# MCU023_XDS110_USB_Power.net
KiCad netlist of a schematic drawn in Altium Designer
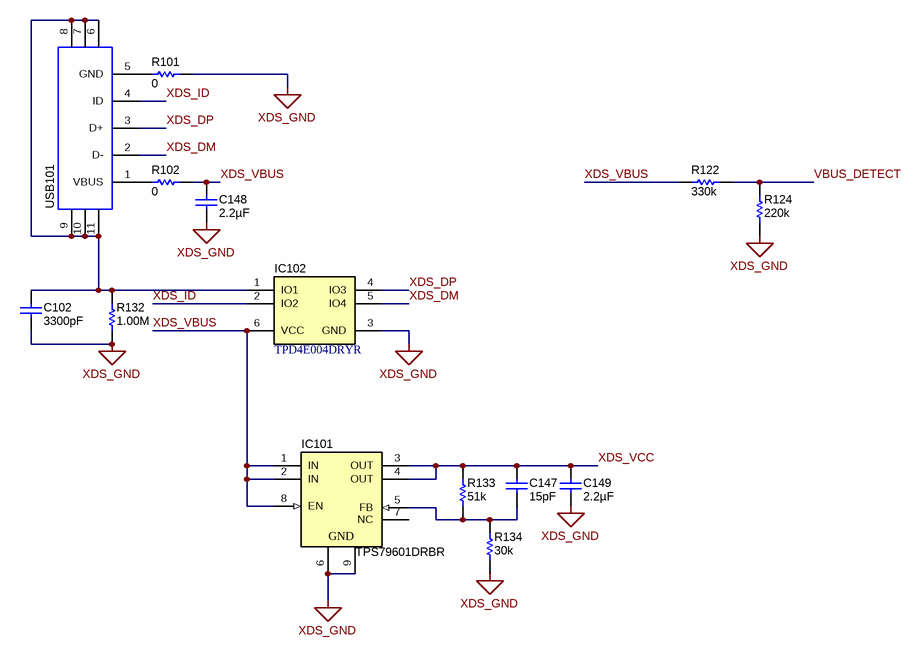
[diagram p0: MCU023_XDS110_USB_Power.SchDoc]

(export (version "E")
  (design (tool "Eeschema 10.0.6"))
  (components
    (comp (ref "C102")
      (value "GRM155R71H332KA01D")
      (footprint "0402")
      (description "CAP, CERM, 3300 pF, 50 V, +/- 10%, X7R, 0402")
      (fields
        (field (name "VALUEDISPLAYED") "3300pF")
        (field (name "MANUFACTURER") "MuRata")
        (field (name "PUBLISHER") "Texas Instruments")
      )
      (libsource (lib "Capacitor_Ceramic") (part "GRM155R71H332KA01D"))
    )
    (comp (ref "C147")
      (value "GRM1555C1H150JA01D")
      (footprint "0402")
      (description "CAP, CERM, 15 pF, 50 V, +/- 5%, C0G/NP0, 0402")
      (fields
        (field (name "VALUEDISPLAYED") "15pF")
        (field (name "MANUFACTURER") "MuRata")
        (field (name "PUBLISHER") "Texas Instruments")
      )
      (libsource (lib "Capacitor_Ceramic") (part "GRM1555C1H150JA01D"))
    )
    (comp (ref "C148")
      (value "GRM155R60J225KE95D")
      (footprint "0402")
      (description "CAP, CERM, 2.2 µF, 6.3 V, +/- 10%, X5R, 0402")
      (fields
        (field (name "VALUEDISPLAYED") "2.2µF")
        (field (name "MANUFACTURER") "MuRata")
        (field (name "PUBLISHER") "Texas Instruments")
      )
      (libsource (lib "Capacitor_Ceramic") (part "GRM155R60J225KE95D"))
    )
    (comp (ref "C149")
      (value "GRM155R60J225KE95D")
      (footprint "0402")
      (description "CAP, CERM, 2.2 µF, 6.3 V, +/- 10%, X5R, 0402")
      (fields
        (field (name "VALUEDISPLAYED") "2.2µF")
        (field (name "MANUFACTURER") "MuRata")
        (field (name "PUBLISHER") "Texas Instruments")
      )
      (libsource (lib "Capacitor_Ceramic") (part "GRM155R60J225KE95D"))
    )
    (comp (ref "IC101")
      (value "TPS79601DRBR")
      (footprint "DRB0008B")
      (fields
        (field (name "MANUFACTURER") "Texas Instruments")
        (field (name "ALTERNATE PARTNUMBER") "Equivalent")
      )
      (libsource (lib "TI Power Management Linear Regulator Single Channel LDO (400-7500mA)") (part "TPS79601DRBR"))
    )
    (comp (ref "IC102")
      (value "TPD4E004DRYR")
      (footprint "DRY0006A")
      (fields
        (field (name "MANUFACTURER") "Texas Instruments")
        (field (name "ALTERNATE PARTNUMBER") "Equivalent")
      )
      (libsource (lib "TI Interface ESD EMI Protection") (part "TPD4E004DRYR"))
    )
    (comp (ref "R101")
      (value "CRCW06030000Z0EA")
      (footprint "0603")
      (description "RES, 0, 5%, 0.1 W, 0603")
      (fields
        (field (name "VALUEDISPLAYED") "0")
        (field (name "MANUFACTURER") "Vishay-Dale")
        (field (name "PUBLISHER") "Texas Instruments")
      )
      (libsource (lib "Resistor_0603") (part "CRCW06030000Z0EA"))
    )
    (comp (ref "R102")
      (value "CRCW06030000Z0EA")
      (footprint "0603")
      (description "RES, 0, 5%, 0.1 W, 0603")
      (fields
        (field (name "VALUEDISPLAYED") "0")
        (field (name "MANUFACTURER") "Vishay-Dale")
        (field (name "PUBLISHER") "Texas Instruments")
      )
      (libsource (lib "Resistor_0603") (part "CRCW06030000Z0EA"))
    )
    (comp (ref "R122")
      (value "RC0402FR-07330KL")
      (footprint "0402")
      (description "RES, 330 k, 1%, 0.0625 W, 0402")
      (fields
        (field (name "VALUEDISPLAYED") "330k")
        (field (name "MANUFACTURER") "Yageo America")
        (field (name "PUBLISHER") "Texas Instruments")
      )
      (libsource (lib "Resistor_0402") (part "RC0402FR-07330KL"))
    )
    (comp (ref "R124")
      (value "RC0402FR-07220KL")
      (footprint "0402")
      (description "RES, 220 k, 1%, 0.0625 W, 0402")
      (fields
        (field (name "VALUEDISPLAYED") "220k")
        (field (name "MANUFACTURER") "Yageo America")
        (field (name "PUBLISHER") "Texas Instruments")
      )
      (libsource (lib "Resistor_0402") (part "RC0402FR-07220KL"))
    )
    (comp (ref "R132")
      (value "CRCW04021M00FKED")
      (footprint "0402")
      (description "RES, 1.00 M, 1%, 0.063 W, 0402")
      (fields
        (field (name "VALUEDISPLAYED") "1.00M")
        (field (name "MANUFACTURER") "Vishay-Dale")
        (field (name "PUBLISHER") "Texas Instruments")
      )
      (libsource (lib "Resistor_0402") (part "CRCW04021M00FKED"))
    )
    (comp (ref "R133")
      (value "CRCW040251K0JNED")
      (footprint "0402")
      (description "RES, 51 k, 5%, 0.063 W, 0402")
      (fields
        (field (name "VALUEDISPLAYED") "51k")
        (field (name "MANUFACTURER") "Vishay-Dale")
        (field (name "PUBLISHER") "Texas Instruments")
      )
      (libsource (lib "Resistor_0402") (part "CRCW040251K0JNED"))
    )
    (comp (ref "R134")
      (value "CRCW040230K0JNED")
      (footprint "0402")
      (description "RES, 30 k, 5%, 0.063 W, 0402")
      (fields
        (field (name "VALUEDISPLAYED") "30k")
        (field (name "MANUFACTURER") "Vishay-Dale")
        (field (name "PUBLISHER") "Texas Instruments")
      )
      (libsource (lib "Resistor_0402") (part "CRCW040230K0JNED"))
    )
    (comp (ref "USB101")
      (value "1051640001")
      (footprint "Molex_1051640001")
      (description "Receptacle, USB 2.0, Micro B, 5 Position, R/A, SMT")
      (fields
        (field (name "MANUFACTURER") "Molex")
        (field (name "SYMBOLCREATOR") "a0411947")
        (field (name "PUBLISHER") "Texas Instruments")
      )
      (libsource (lib "Connectors_Molex") (part "1051640001"))
    )
  )
  (nets
    (net (code "1") (name "/VBUS_DETECT") (class "Default")
      (node (ref "R122") (pin "1") (pinfunction "1_1") (pintype "passive"))
      (node (ref "R124") (pin "2") (pinfunction "2_2") (pintype "passive"))
    )
    (net (code "2") (name "/XDS_DM") (class "Default")
      (node (ref "IC102") (pin "5") (pinfunction "IO4_5") (pintype "passive"))
      (node (ref "USB101") (pin "2") (pinfunction "D-_2") (pintype "passive"))
    )
    (net (code "3") (name "/XDS_DP") (class "Default")
      (node (ref "IC102") (pin "4") (pinfunction "IO3_4") (pintype "passive"))
      (node (ref "USB101") (pin "3") (pinfunction "D+_3") (pintype "passive"))
    )
    (net (code "4") (name "/XDS_ID") (class "Default")
      (node (ref "IC102") (pin "2") (pinfunction "IO2_2") (pintype "passive"))
      (node (ref "USB101") (pin "4") (pinfunction "ID_4") (pintype "passive"))
    )
    (net (code "5") (name "/XDS_VBUS") (class "Default")
      (node (ref "C148") (pin "1") (pinfunction "1_1") (pintype "passive"))
      (node (ref "IC101") (pin "1") (pinfunction "IN_1") (pintype "power_in"))
      (node (ref "IC101") (pin "2") (pinfunction "IN_2") (pintype "power_in"))
      (node (ref "IC101") (pin "8") (pinfunction "EN_8") (pintype "input"))
      (node (ref "IC102") (pin "6") (pinfunction "VCC_6") (pintype "power_in"))
      (node (ref "R102") (pin "2") (pinfunction "2_2") (pintype "passive"))
      (node (ref "R122") (pin "2") (pinfunction "2_2") (pintype "passive"))
    )
    (net (code "6") (name "/XDS_VCC") (class "Default")
      (node (ref "C147") (pin "1") (pinfunction "1_1") (pintype "passive"))
      (node (ref "C149") (pin "1") (pinfunction "1_1") (pintype "passive"))
      (node (ref "IC101") (pin "3") (pinfunction "OUT_3") (pintype "power_in"))
      (node (ref "IC101") (pin "4") (pinfunction "OUT_4") (pintype "power_in"))
      (node (ref "R133") (pin "2") (pinfunction "2_2") (pintype "passive"))
    )
    (net (code "7") (name "Net-(IC101-FB)") (class "Default")
      (node (ref "C147") (pin "2") (pinfunction "2_2") (pintype "passive"))
      (node (ref "IC101") (pin "5") (pinfunction "FB_5") (pintype "input"))
      (node (ref "R133") (pin "1") (pinfunction "1_1") (pintype "passive"))
      (node (ref "R134") (pin "2") (pinfunction "2_2") (pintype "passive"))
    )
    (net (code "8") (name "Net-(IC102-IO1)") (class "Default")
      (node (ref "C102") (pin "1") (pinfunction "1_1") (pintype "passive"))
      (node (ref "IC102") (pin "1") (pinfunction "IO1_1") (pintype "passive"))
      (node (ref "R132") (pin "2") (pinfunction "2_2") (pintype "passive"))
      (node (ref "USB101") (pin "10") (pinfunction "10_10") (pintype "passive"))
      (node (ref "USB101") (pin "11") (pinfunction "11_11") (pintype "passive"))
      (node (ref "USB101") (pin "6") (pinfunction "6_6") (pintype "passive"))
      (node (ref "USB101") (pin "7") (pinfunction "7_7") (pintype "passive"))
      (node (ref "USB101") (pin "8") (pinfunction "8_8") (pintype "passive"))
      (node (ref "USB101") (pin "9") (pinfunction "9_9") (pintype "passive"))
    )
    (net (code "9") (name "Net-(USB101-GND)") (class "Default")
      (node (ref "R101") (pin "1") (pinfunction "1_1") (pintype "passive"))
      (node (ref "USB101") (pin "5") (pinfunction "GND_5") (pintype "passive"))
    )
    (net (code "10") (name "Net-(USB101-VBUS)") (class "Default")
      (node (ref "R102") (pin "1") (pinfunction "1_1") (pintype "passive"))
      (node (ref "USB101") (pin "1") (pinfunction "VBUS_1") (pintype "passive"))
    )
    (net (code "11") (name "XDS_GND") (class "Default")
      (node (ref "C102") (pin "2") (pinfunction "2_2") (pintype "passive"))
      (node (ref "C148") (pin "2") (pinfunction "2_2") (pintype "passive"))
      (node (ref "C149") (pin "2") (pinfunction "2_2") (pintype "passive"))
      (node (ref "IC101") (pin "6") (pinfunction "GND_6") (pintype "power_in"))
      (node (ref "IC101") (pin "9") (pinfunction "GND_9") (pintype "power_in"))
      (node (ref "IC102") (pin "3") (pinfunction "GND_3") (pintype "power_in"))
      (node (ref "R101") (pin "2") (pinfunction "2_2") (pintype "passive"))
      (node (ref "R124") (pin "1") (pinfunction "1_1") (pintype "passive"))
      (node (ref "R132") (pin "1") (pinfunction "1_1") (pintype "passive"))
      (node (ref "R134") (pin "1") (pinfunction "1_1") (pintype "passive"))
    )
    (net (code "12") (name "unconnected-(IC101-NC-Pad7)") (class "Default")
      (node (ref "IC101") (pin "7") (pinfunction "NC_7") (pintype "passive"))
    )
  )
)
